# 1_Supply.net
KiCad netlist of a schematic drawn in Altium Designer
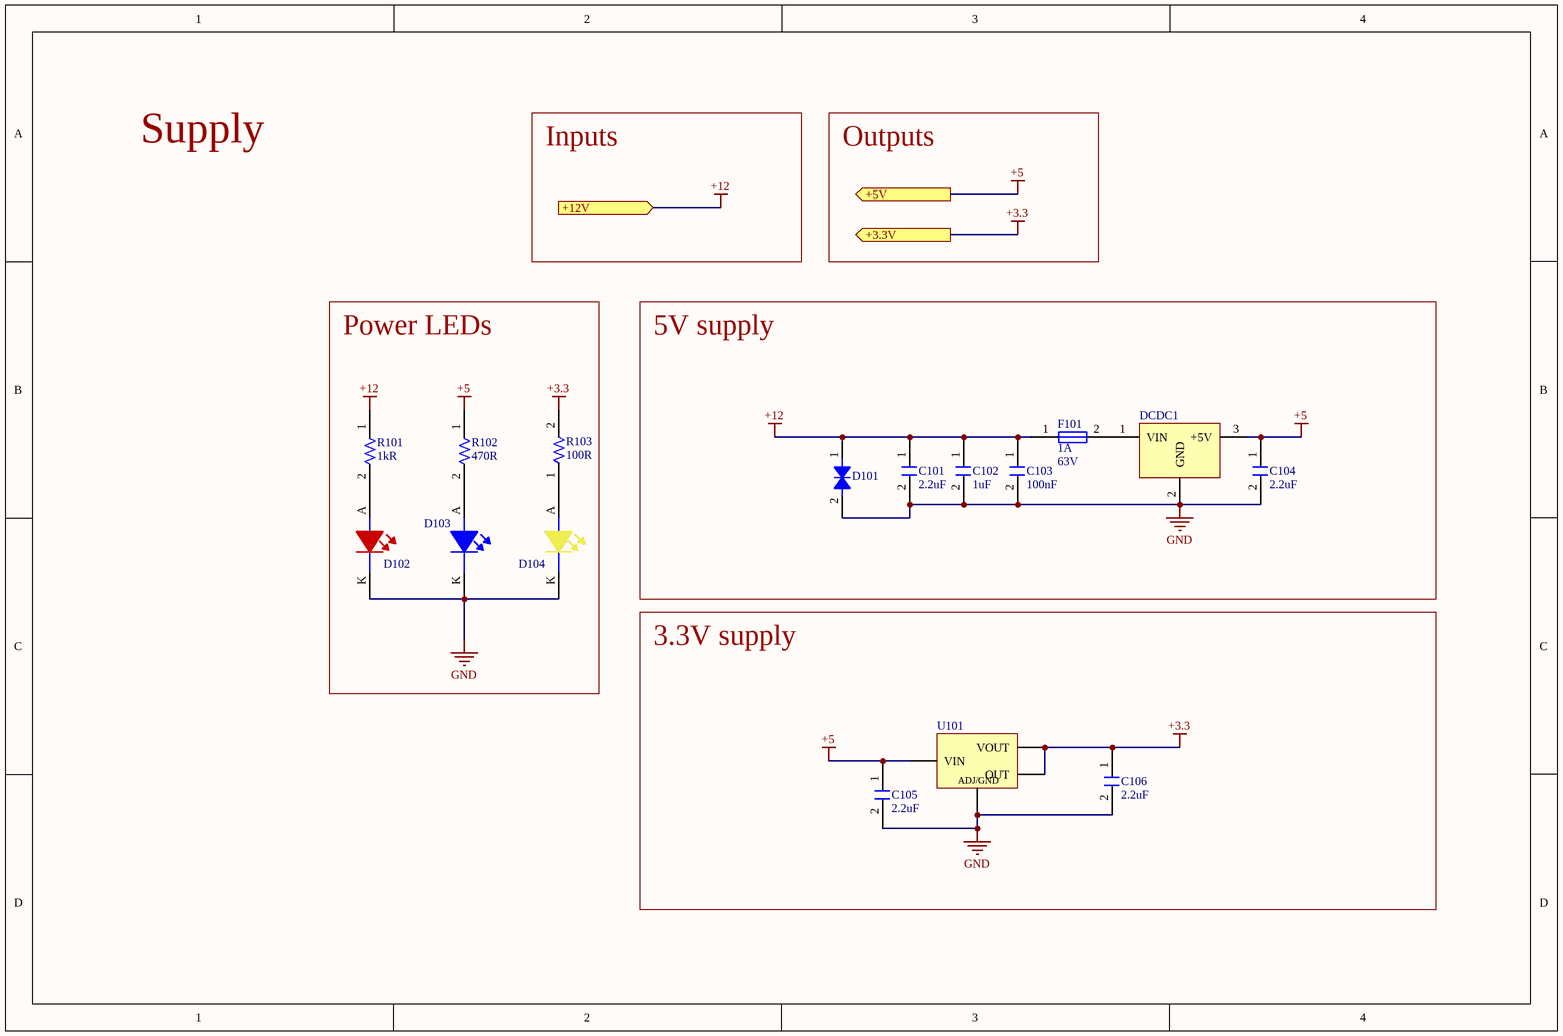
[diagram p0: [1]Supply.SchDoc]

(export (version "E")
  (design (tool "Eeschema 10.0.6"))
  (components
    (comp (ref "C101")
      (value "2.2uF")
      (footprint "C0805FNPC-W")
      (libsource (lib "Passives") (part "C2.2u-16V-0805FTK"))
    )
    (comp (ref "C102")
      (value "885012208036")
      (footprint "C1206FNPC-RW")
      (description "Cap Cer 1UF 16V X7R 1206")
      (fields
        (field (name "MANUFACTURER") "Wurth Electronics")
        (field (name "TOLERANCE") "10%")
        (field (name "CAPACITANCE") "1uF")
        (field (name ".CREATOR") "GP")
      )
      (libsource (lib "Passives") (part "C1u-16V-1206FNPC-X7R"))
    )
    (comp (ref "C103")
      (value "885012207098")
      (footprint "C0805FNPC-R")
      (description "Cap, 0.1ΜF, 50V, 10%, X7R, 0805")
      (fields
        (field (name "TOLERANCE") "10%")
        (field (name "CAPACITANCE") "100nF")
        (field (name ".CREATOR") "DR")
      )
      (libsource (lib "Passives") (part "C100n-50V-0805FNPC-X7R"))
    )
    (comp (ref "C104")
      (value "2.2uF")
      (footprint "C0805FNPC-W")
      (libsource (lib "Passives") (part "C2.2u-16V-0805FTK"))
    )
    (comp (ref "C105")
      (value "2.2uF")
      (footprint "C0805FNPC-W")
      (libsource (lib "Passives") (part "C2.2u-16V-0805FTK"))
    )
    (comp (ref "C106")
      (value "2.2uF")
      (footprint "C0805FNPC-W")
      (libsource (lib "Passives") (part "C2.2u-16V-0805FTK"))
    )
    (comp (ref "D101")
      (value "824501261")
      (footprint "DTVS-DO-214AC")
      (description "TVS diode [Würth Elektronik] 824501261 TVS diode")
      (fields (field (name "MANUFACTURER") "Wurth Electronics") (field (name ".CREATOR") "DO"))
      (libsource (lib "Filter components") (part "DTVS-26V-DO-214AC"))
    )
    (comp (ref "D102")
      (value "150080RS75000")
      (footprint "LED_0805_WE")
      (description "0805(H=0.8mm) 红色 高亮 λD=625nm VF=2V IF=30mA PD=72mW")
      (fields (field (name ".CREATOR") "DR"))
      (libsource (lib "Semiconductor") (part "LEDRS-0805-150"))
    )
    (comp (ref "D103")
      (value "150080BS75000")
      (footprint "LED_0805_WE")
      (description "LED BLUE CLEAR 0805 SMD")
      (fields (field (name ".CREATOR") "GP"))
      (libsource (lib "Semiconductor") (part "LEDBS-0805-145"))
    )
    (comp (ref "D104")
      (value "150080YS75000")
      (footprint "LED_0805_WE")
      (description "2 V Yellow LED 2012 (0805) SMD, Wurth Elektronik WL-SMCW 150080YS75000")
      (fields (field (name ".CREATOR") "DR"))
      (libsource (lib "Semiconductor") (part "LEDYS-0805-120"))
    )
    (comp (ref "DCDC1")
      (value "173010542")
      (footprint "DCDC_Magi3c")
      (description "Würth Elektronik 8-42V to 5V 1A DC-DC")
      (fields (field (name ".CREATOR") "DR"))
      (libsource (lib "Semiconductor") (part "DCDC-42V/5V-1A"))
    )
    (comp (ref "F101")
      (value "0437001.WRA")
      (footprint "Fuse_1206")
      (description "Fuse Chip Fast Acting 1A 63V SMD Solder Pad 1206 Ceramic T/R Automotive")
      (fields
        (field (name "MANUFACTURER") "Littelfuse")
        (field (name "CURRENT RATING") "1A")
        (field (name "VOLTAGE RATING (DC)") "63V")
        (field (name ".CREATOR") "DO")
      )
      (libsource (lib "Filter components") (part "Fuse_1A_63V_1206"))
    )
    (comp (ref "R101")
      (value "CR0805-JW-102ELF")
      (footprint "R0805FTK")
      (description "Res Thick Film 0805 1K Ohm 5% 1/8W ±200ppm/°C Molded SMD SMD Paper Tape on Plastic Reel")
      (fields
        (field (name "TOLERANCE") "5%")
        (field (name "RESISTANCE") "1kR")
        (field (name ".CREATOR") "GP")
      )
      (libsource (lib "Passives") (part "R1k-0805FTK"))
    )
    (comp (ref "R102")
      (value "CR0805-FX-4700GLF")
      (footprint "R0805FTK")
      (description "Res Thick Film 0805 470 Ohm 1% 1/8W ±100ppm/°C Molded SMD SMD Paper Tape on Plastic Reel")
      (fields
        (field (name "TOLERANCE") "1%")
        (field (name "RESISTANCE") "470R")
        (field (name ".CREATOR") "DR")
      )
      (libsource (lib "Passives") (part "R470-0805FTK"))
    )
    (comp (ref "R103")
      (value "CR0805-FX-1000ELF")
      (footprint "R0805FTK")
      (description "Res Thick Film 0805 100 Ohm 1% 1/8W ±100ppm/°C Molded SMD SMD Paper Tape on Plastic Reel")
      (fields
        (field (name "TOLERANCE") "1%")
        (field (name "RESISTANCE") "100R")
        (field (name ".CREATOR") "DR")
      )
      (libsource (lib "Passives") (part "R100-0805FTK"))
    )
    (comp (ref "U101")
      (value "LM1117IMP-3.3/NOPB")
      (footprint "LDO_10V-0.8/3V3-SOT223")
      (description "LDO Regulator Pos 3.3V 0.8A 4-Pin(3+Tab) SOT-223 T/R / IC REG LDO 3.3V 0.8A SOT223")
      (fields (field (name "MANUFACTURER") "Texas Instruments") (field (name ".CREATOR") "GP"))
      (libsource (lib "Semiconductor") (part "LDO_10V-0.8/3V3-SOT223"))
    )
  )
  (nets
    (net (code "1") (name "+3.3") (class "Default")
      (node (ref "C106") (pin "1") (pinfunction "1_1") (pintype "passive"))
      (node (ref "R103") (pin "2") (pinfunction "2_2") (pintype "passive"))
      (node (ref "U101") (pin "2") (pinfunction "OUT_2") (pintype "passive"))
      (node (ref "U101") (pin "4") (pinfunction "VOUT_4") (pintype "passive"))
    )
    (net (code "2") (name "+5") (class "Default")
      (node (ref "C104") (pin "1") (pinfunction "1_1") (pintype "passive"))
      (node (ref "C105") (pin "1") (pinfunction "1_1") (pintype "passive"))
      (node (ref "DCDC1") (pin "3") (pinfunction "+5V_3") (pintype "passive"))
      (node (ref "R102") (pin "1") (pinfunction "1_1") (pintype "passive"))
      (node (ref "U101") (pin "3") (pinfunction "VIN_3") (pintype "passive"))
    )
    (net (code "3") (name "+12") (class "Default")
      (node (ref "C101") (pin "1") (pinfunction "1_1") (pintype "passive"))
      (node (ref "C102") (pin "1") (pinfunction "1_1") (pintype "passive"))
      (node (ref "C103") (pin "1") (pinfunction "1_1") (pintype "passive"))
      (node (ref "D101") (pin "1") (pinfunction "1_1") (pintype "passive"))
      (node (ref "F101") (pin "1") (pinfunction "1_1") (pintype "passive"))
      (node (ref "R101") (pin "1") (pinfunction "1_1") (pintype "passive"))
    )
    (net (code "4") (name "GND") (class "Default")
      (node (ref "C101") (pin "2") (pinfunction "2_2") (pintype "passive"))
      (node (ref "C102") (pin "2") (pinfunction "2_2") (pintype "passive"))
      (node (ref "C103") (pin "2") (pinfunction "2_2") (pintype "passive"))
      (node (ref "C104") (pin "2") (pinfunction "2_2") (pintype "passive"))
      (node (ref "C105") (pin "2") (pinfunction "2_2") (pintype "passive"))
      (node (ref "C106") (pin "2") (pinfunction "2_2") (pintype "passive"))
      (node (ref "D101") (pin "2") (pinfunction "2_2") (pintype "passive"))
      (node (ref "D102") (pin "K") (pinfunction "K_K") (pintype "passive"))
      (node (ref "D103") (pin "K") (pinfunction "K_K") (pintype "passive"))
      (node (ref "D104") (pin "K") (pinfunction "K_K") (pintype "passive"))
      (node (ref "DCDC1") (pin "2") (pinfunction "GND_2") (pintype "passive"))
      (node (ref "U101") (pin "1") (pinfunction "ADJ/GND_1") (pintype "passive"))
    )
    (net (code "5") (name "Net-(D102-PadA)") (class "Default")
      (node (ref "D102") (pin "A") (pinfunction "A_A") (pintype "passive"))
      (node (ref "R101") (pin "2") (pinfunction "2_2") (pintype "passive"))
    )
    (net (code "6") (name "Net-(D103-PadA)") (class "Default")
      (node (ref "D103") (pin "A") (pinfunction "A_A") (pintype "passive"))
      (node (ref "R102") (pin "2") (pinfunction "2_2") (pintype "passive"))
    )
    (net (code "7") (name "Net-(D104-PadA)") (class "Default")
      (node (ref "D104") (pin "A") (pinfunction "A_A") (pintype "passive"))
      (node (ref "R103") (pin "1") (pinfunction "1_1") (pintype "passive"))
    )
    (net (code "8") (name "Net-(DCDC1-VIN)") (class "Default")
      (node (ref "DCDC1") (pin "1") (pinfunction "VIN_1") (pintype "passive"))
      (node (ref "F101") (pin "2") (pinfunction "2_2") (pintype "passive"))
    )
  )
)
